# Pure_VCF.net
KiCad netlist of a schematic drawn in EAGLE
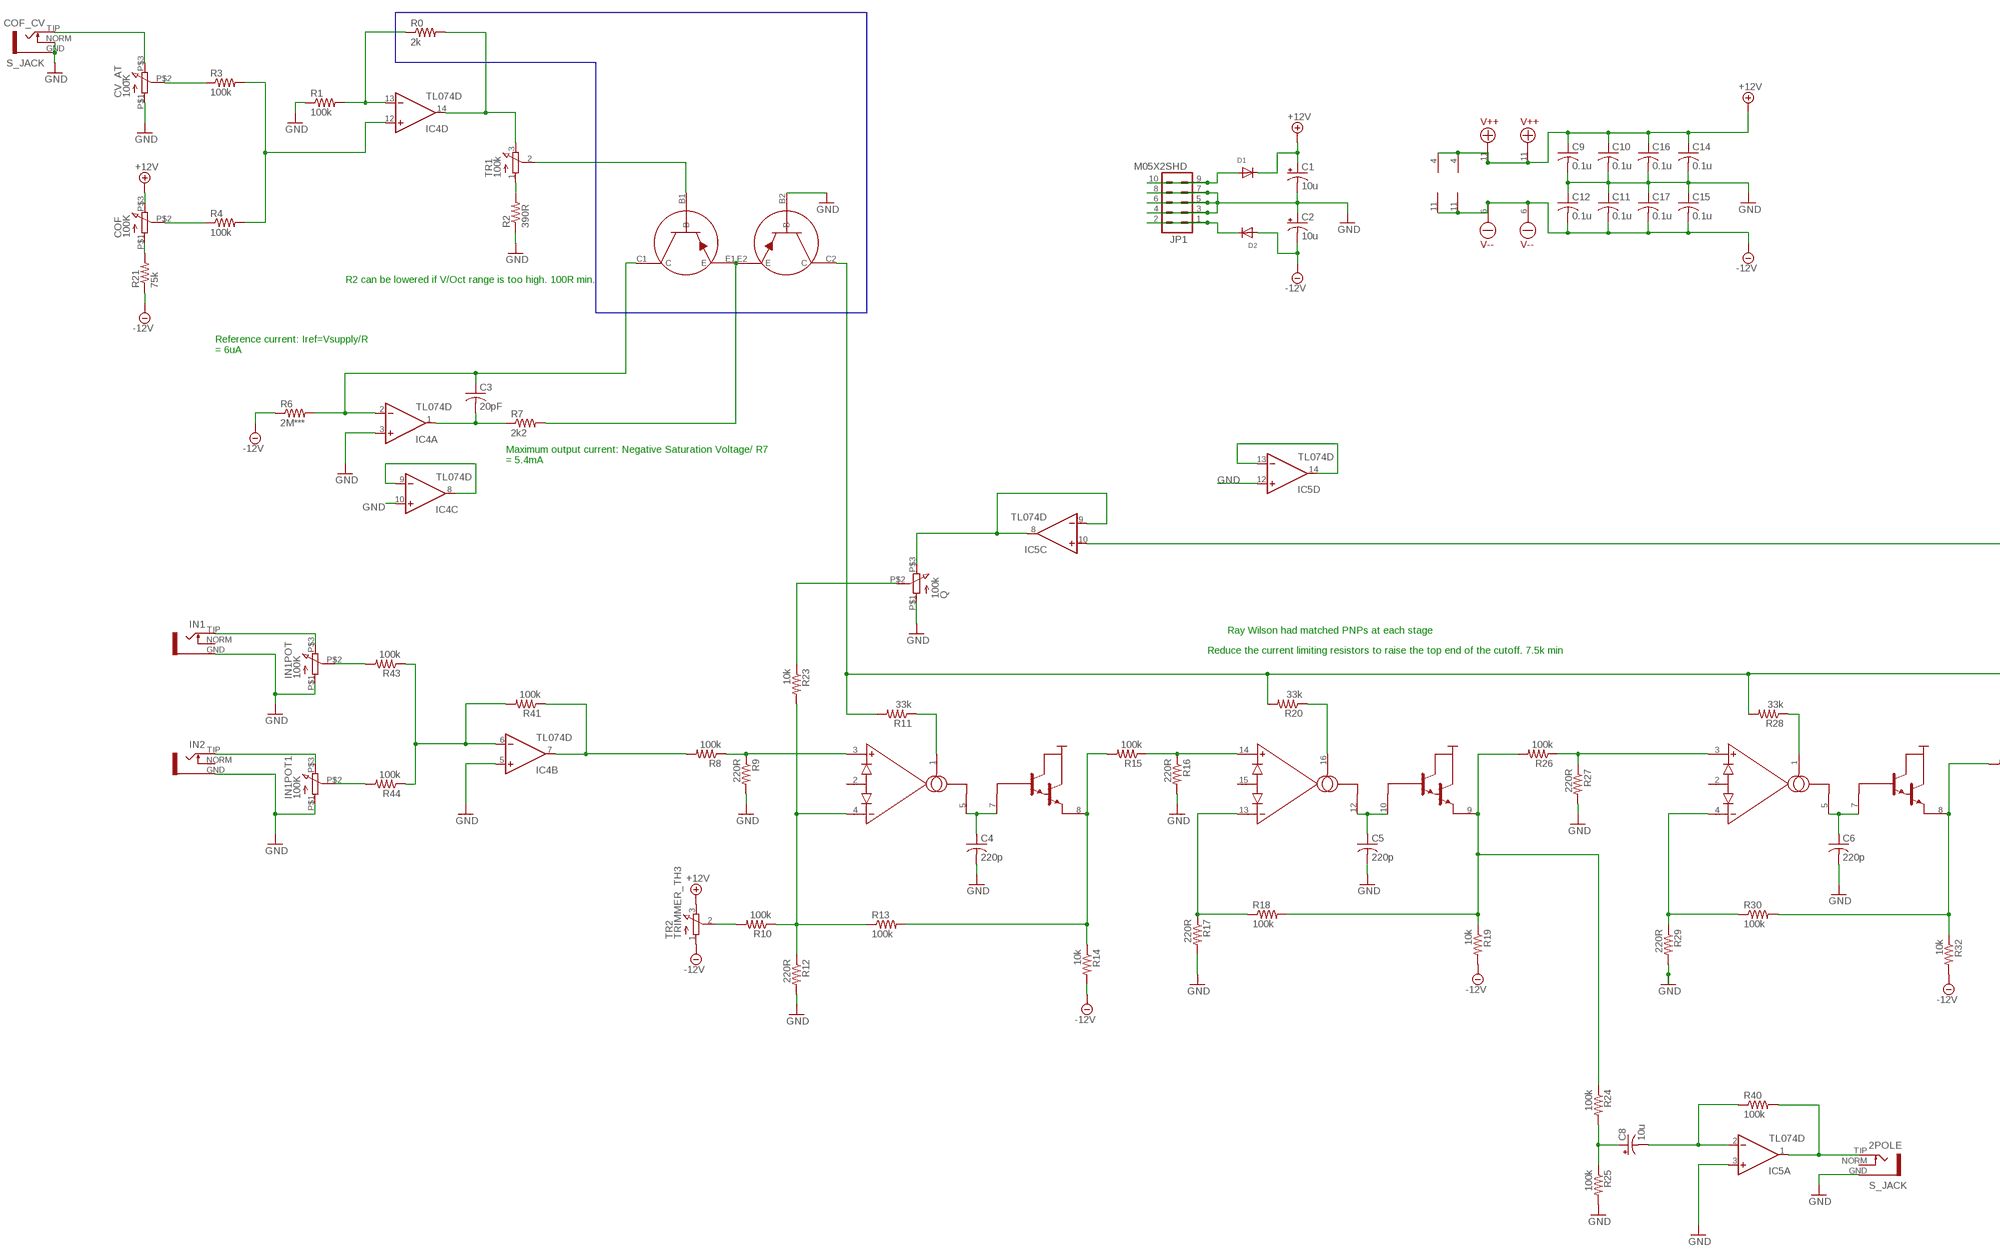
[diagram p0: schematic, sheet 1, part 1 of 2]
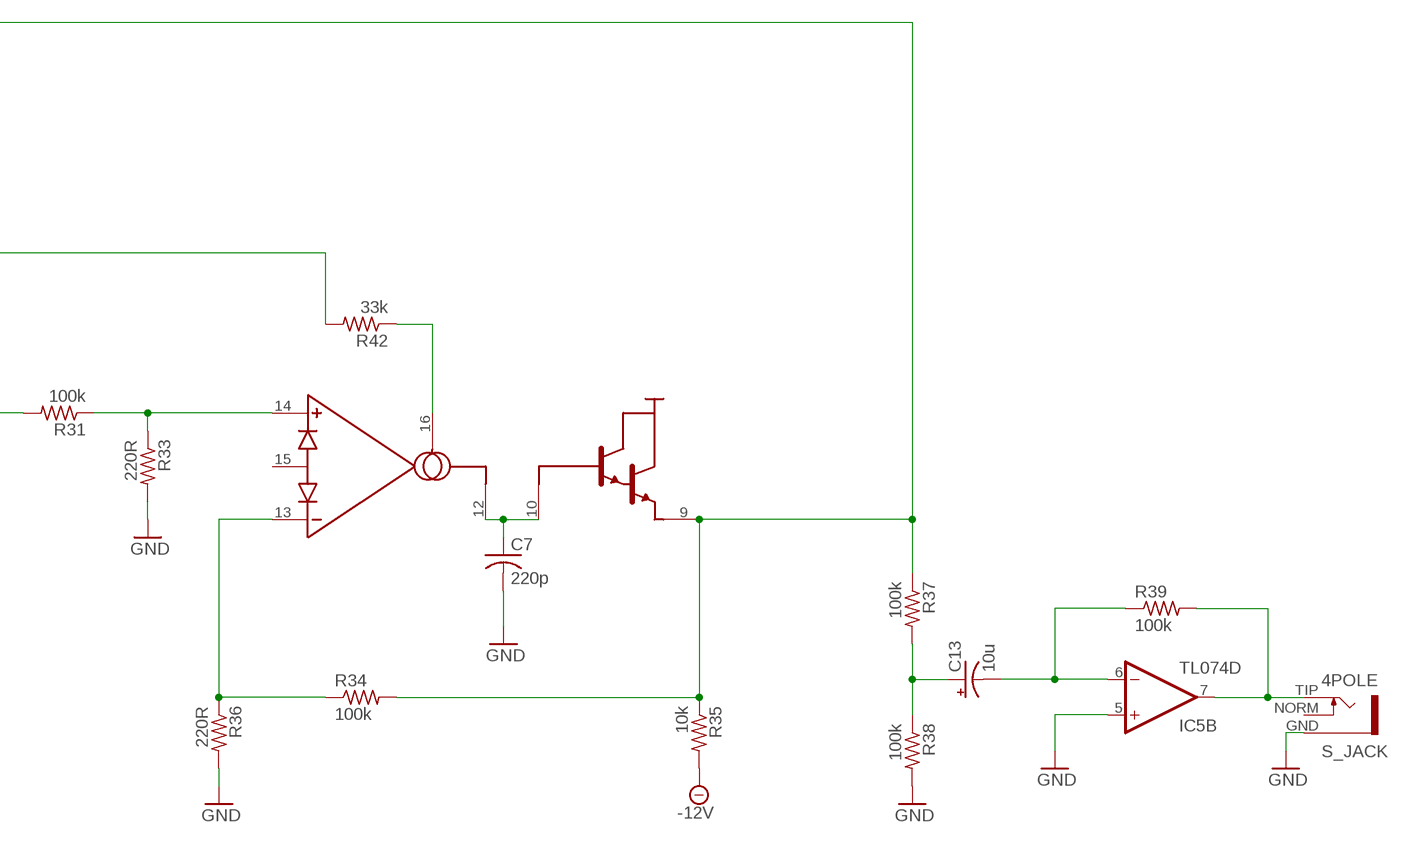
[diagram p1: schematic, sheet 1, part 2 of 2]

(export (version "E")
  (design (tool "Eeschema 10.0.6"))
  (components
    (comp (ref "2POLE")
      (value "S_JACK")
      (footprint "eagle-import:S_JACK")
      (libsource (lib "eagle-import") (part "S_JACK"))
    )
    (comp (ref "4POLE")
      (value "S_JACK")
      (footprint "eagle-import:S_JACK")
      (libsource (lib "eagle-import") (part "S_JACK"))
    )
    (comp (ref "C1")
      (value "10u")
      (footprint "eagle-import:153CLV-0505")
      (libsource (lib "eagle-import") (part "rcl_CPOL-US153CLV-0505"))
    )
    (comp (ref "C2")
      (value "10u")
      (footprint "eagle-import:153CLV-0505")
      (libsource (lib "eagle-import") (part "rcl_CPOL-US153CLV-0505"))
    )
    (comp (ref "C3")
      (value "20pF")
      (footprint "eagle-import:C0805K")
      (libsource (lib "eagle-import") (part "C-USC0805K"))
    )
    (comp (ref "C4")
      (value "220p")
      (footprint "eagle-import:C050-045X075")
      (libsource (lib "eagle-import") (part "rcl_C-US050-045X075"))
    )
    (comp (ref "C5")
      (value "220p")
      (footprint "eagle-import:C050-045X075")
      (libsource (lib "eagle-import") (part "rcl_C-US050-045X075"))
    )
    (comp (ref "C6")
      (value "220p")
      (footprint "eagle-import:C050-045X075")
      (libsource (lib "eagle-import") (part "rcl_C-US050-045X075"))
    )
    (comp (ref "C7")
      (value "220p")
      (footprint "eagle-import:C050-045X075")
      (libsource (lib "eagle-import") (part "rcl_C-US050-045X075"))
    )
    (comp (ref "C8")
      (value "10u")
      (footprint "eagle-import:153CLV-0505")
      (libsource (lib "eagle-import") (part "CPOL-US153CLV-0505"))
    )
    (comp (ref "C9")
      (value "0.1u")
      (footprint "eagle-import:C0805K")
      (libsource (lib "eagle-import") (part "rcl_C-USC0805K"))
    )
    (comp (ref "C10")
      (value "0.1u")
      (footprint "eagle-import:C0805K")
      (libsource (lib "eagle-import") (part "rcl_C-USC0805K"))
    )
    (comp (ref "C11")
      (value "0.1u")
      (footprint "eagle-import:C0805K")
      (libsource (lib "eagle-import") (part "rcl_C-USC0805K"))
    )
    (comp (ref "C12")
      (value "0.1u")
      (footprint "eagle-import:C0805K")
      (libsource (lib "eagle-import") (part "rcl_C-USC0805K"))
    )
    (comp (ref "C13")
      (value "10u")
      (footprint "eagle-import:153CLV-0505")
      (libsource (lib "eagle-import") (part "CPOL-US153CLV-0505"))
    )
    (comp (ref "C14")
      (value "0.1u")
      (footprint "eagle-import:C0805K")
      (libsource (lib "eagle-import") (part "rcl_C-USC0805K"))
    )
    (comp (ref "C15")
      (value "0.1u")
      (footprint "eagle-import:C0805K")
      (libsource (lib "eagle-import") (part "rcl_C-USC0805K"))
    )
    (comp (ref "C16")
      (value "0.1u")
      (footprint "eagle-import:C0805K")
      (libsource (lib "eagle-import") (part "rcl_C-USC0805K"))
    )
    (comp (ref "C17")
      (value "0.1u")
      (footprint "eagle-import:C0805K")
      (libsource (lib "eagle-import") (part "rcl_C-USC0805K"))
    )
    (comp (ref "COF")
      (value "100K")
      (footprint "eagle-import:POT")
      (libsource (lib "eagle-import") (part "9MMPOT"))
    )
    (comp (ref "COF_CV")
      (value "S_JACK")
      (footprint "eagle-import:S_JACK")
      (libsource (lib "eagle-import") (part "S_JACK"))
    )
    (comp (ref "CV_AT")
      (value "100K")
      (footprint "eagle-import:POT")
      (libsource (lib "eagle-import") (part "9MMPOT"))
    )
    (comp (ref "D1")
      (value "DIODESMA")
      (footprint "eagle-import:SMADIODE")
      (libsource (lib "eagle-import") (part "DIODESMA"))
    )
    (comp (ref "D2")
      (value "DIODESMA")
      (footprint "eagle-import:SMADIODE")
      (libsource (lib "eagle-import") (part "DIODESMA"))
    )
    (comp (ref "IC4")
      (value "TL074D")
      (footprint "eagle-import:SO14")
      (libsource (lib "eagle-import") (part "TL074D"))
    )
    (comp (ref "IC5")
      (value "TL074D")
      (footprint "eagle-import:SO14")
      (libsource (lib "eagle-import") (part "TL074D"))
    )
    (comp (ref "IN1")
      (value "S_JACK")
      (footprint "eagle-import:S_JACK")
      (libsource (lib "eagle-import") (part "INSTRUO_S_JACK"))
    )
    (comp (ref "IN1POT")
      (value "100K")
      (footprint "eagle-import:POT")
      (libsource (lib "eagle-import") (part "9MMPOT"))
    )
    (comp (ref "IN1POT1")
      (value "100K")
      (footprint "eagle-import:POT")
      (libsource (lib "eagle-import") (part "9MMPOT"))
    )
    (comp (ref "IN2")
      (value "S_JACK")
      (footprint "eagle-import:S_JACK")
      (libsource (lib "eagle-import") (part "INSTRUO_S_JACK"))
    )
    (comp (ref "JP1")
      (value "M05X2SHD")
      (footprint "eagle-import:2X5-SHROUDED")
      (libsource (lib "eagle-import") (part "M05X2SHD"))
    )
    (comp (ref "Q")
      (value "100k")
      (footprint "eagle-import:POT")
      (libsource (lib "eagle-import") (part "9MMPOT"))
    )
    (comp (ref "R0")
      (value "2k")
      (footprint "eagle-import:RESISTOR_TC")
      (libsource (lib "eagle-import") (part "R_TC"))
    )
    (comp (ref "R1")
      (value "100k")
      (footprint "eagle-import:R0805")
      (libsource (lib "eagle-import") (part "R-US_R0805"))
    )
    (comp (ref "R2")
      (value "390R")
      (footprint "eagle-import:R0805")
      (libsource (lib "eagle-import") (part "R-US_R0805"))
    )
    (comp (ref "R3")
      (value "100k")
      (footprint "eagle-import:R0805")
      (libsource (lib "eagle-import") (part "R-US_R0805"))
    )
    (comp (ref "R4")
      (value "100k")
      (footprint "eagle-import:R0805")
      (libsource (lib "eagle-import") (part "R-US_R0805"))
    )
    (comp (ref "R6")
      (value "2M***")
      (footprint "eagle-import:R0805")
      (libsource (lib "eagle-import") (part "R-US_R0805"))
    )
    (comp (ref "R7")
      (value "2k2")
      (footprint "eagle-import:R0805")
      (libsource (lib "eagle-import") (part "R-US_R0805"))
    )
    (comp (ref "R8")
      (value "100k")
      (footprint "eagle-import:R0805")
      (libsource (lib "eagle-import") (part "R-US_R0805"))
    )
    (comp (ref "R9")
      (value "220R")
      (footprint "eagle-import:R0805")
      (libsource (lib "eagle-import") (part "R-US_R0805"))
    )
    (comp (ref "R10")
      (value "100k")
      (footprint "eagle-import:R0805")
      (libsource (lib "eagle-import") (part "R-US_R0805"))
    )
    (comp (ref "R11")
      (value "33k")
      (footprint "eagle-import:R0805")
      (libsource (lib "eagle-import") (part "R-US_R0805"))
    )
    (comp (ref "R12")
      (value "220R")
      (footprint "eagle-import:R0805")
      (libsource (lib "eagle-import") (part "R-US_R0805"))
    )
    (comp (ref "R13")
      (value "100k")
      (footprint "eagle-import:R0805")
      (libsource (lib "eagle-import") (part "R-US_R0805"))
    )
    (comp (ref "R14")
      (value "10k")
      (footprint "eagle-import:R0805")
      (libsource (lib "eagle-import") (part "R-US_R0805"))
    )
    (comp (ref "R15")
      (value "100k")
      (footprint "eagle-import:R0805")
      (libsource (lib "eagle-import") (part "R-US_R0805"))
    )
    (comp (ref "R16")
      (value "220R")
      (footprint "eagle-import:R0805")
      (libsource (lib "eagle-import") (part "R-US_R0805"))
    )
    (comp (ref "R17")
      (value "220R")
      (footprint "eagle-import:R0805")
      (libsource (lib "eagle-import") (part "R-US_R0805"))
    )
    (comp (ref "R18")
      (value "100k")
      (footprint "eagle-import:R0805")
      (libsource (lib "eagle-import") (part "R-US_R0805"))
    )
    (comp (ref "R19")
      (value "10k")
      (footprint "eagle-import:R0805")
      (libsource (lib "eagle-import") (part "R-US_R0805"))
    )
    (comp (ref "R20")
      (value "33k")
      (footprint "eagle-import:R0805")
      (libsource (lib "eagle-import") (part "R-US_R0805"))
    )
    (comp (ref "R21")
      (value "75k")
      (footprint "eagle-import:R0805")
      (libsource (lib "eagle-import") (part "rcl_R-US_R0805"))
    )
    (comp (ref "R23")
      (value "10k")
      (footprint "eagle-import:R0805")
      (libsource (lib "eagle-import") (part "R-US_R0805"))
    )
    (comp (ref "R24")
      (value "100k")
      (footprint "eagle-import:R0805")
      (libsource (lib "eagle-import") (part "R-US_R0805"))
    )
    (comp (ref "R25")
      (value "100k")
      (footprint "eagle-import:R0805")
      (libsource (lib "eagle-import") (part "R-US_R0805"))
    )
    (comp (ref "R26")
      (value "100k")
      (footprint "eagle-import:R0805")
      (libsource (lib "eagle-import") (part "R-US_R0805"))
    )
    (comp (ref "R27")
      (value "220R")
      (footprint "eagle-import:R0805")
      (libsource (lib "eagle-import") (part "R-US_R0805"))
    )
    (comp (ref "R28")
      (value "33k")
      (footprint "eagle-import:R0805")
      (libsource (lib "eagle-import") (part "R-US_R0805"))
    )
    (comp (ref "R29")
      (value "220R")
      (footprint "eagle-import:R0805")
      (libsource (lib "eagle-import") (part "R-US_R0805"))
    )
    (comp (ref "R30")
      (value "100k")
      (footprint "eagle-import:R0805")
      (libsource (lib "eagle-import") (part "R-US_R0805"))
    )
    (comp (ref "R31")
      (value "100k")
      (footprint "eagle-import:R0805")
      (libsource (lib "eagle-import") (part "R-US_R0805"))
    )
    (comp (ref "R32")
      (value "10k")
      (footprint "eagle-import:R0805")
      (libsource (lib "eagle-import") (part "R-US_R0805"))
    )
    (comp (ref "R33")
      (value "220R")
      (footprint "eagle-import:R0805")
      (libsource (lib "eagle-import") (part "R-US_R0805"))
    )
    (comp (ref "R34")
      (value "100k")
      (footprint "eagle-import:R0805")
      (libsource (lib "eagle-import") (part "R-US_R0805"))
    )
    (comp (ref "R35")
      (value "10k")
      (footprint "eagle-import:R0805")
      (libsource (lib "eagle-import") (part "R-US_R0805"))
    )
    (comp (ref "R36")
      (value "220R")
      (footprint "eagle-import:R0805")
      (libsource (lib "eagle-import") (part "R-US_R0805"))
    )
    (comp (ref "R37")
      (value "100k")
      (footprint "eagle-import:R0805")
      (libsource (lib "eagle-import") (part "R-US_R0805"))
    )
    (comp (ref "R38")
      (value "100k")
      (footprint "eagle-import:R0805")
      (libsource (lib "eagle-import") (part "R-US_R0805"))
    )
    (comp (ref "R39")
      (value "100k")
      (footprint "eagle-import:R0805")
      (libsource (lib "eagle-import") (part "R-US_R0805"))
    )
    (comp (ref "R40")
      (value "100k")
      (footprint "eagle-import:R0805")
      (libsource (lib "eagle-import") (part "R-US_R0805"))
    )
    (comp (ref "R41")
      (value "100k")
      (footprint "eagle-import:R0805")
      (libsource (lib "eagle-import") (part "R-US_R0805"))
    )
    (comp (ref "R42")
      (value "33k")
      (footprint "eagle-import:R0805")
      (libsource (lib "eagle-import") (part "R-US_R0805"))
    )
    (comp (ref "R43")
      (value "100k")
      (footprint "eagle-import:R0805")
      (libsource (lib "eagle-import") (part "R-US_R0805"))
    )
    (comp (ref "R44")
      (value "100k")
      (footprint "eagle-import:R0805")
      (libsource (lib "eagle-import") (part "R-US_R0805"))
    )
    (comp (ref "T1")
      (value "TRANS_PAIR_PNP")
      (footprint "eagle-import:TRANS_PAIR")
      (libsource (lib "eagle-import") (part "TRANS_PAIR_PNP"))
    )
    (comp (ref "TR1")
      (value "100k")
      (footprint "eagle-import:TRIMMER_TH3")
      (libsource (lib "eagle-import") (part "TRIMMER_TH3"))
    )
    (comp (ref "TR2")
      (value "TRIMMER_TH3")
      (footprint "eagle-import:TRIMMER_TH3")
      (libsource (lib "eagle-import") (part "TRIMMER_TH3"))
    )
    (comp (ref "U$3")
      (value "LM13700")
      (footprint "eagle-import:SOIC-16_BLANK")
      (libsource (lib "eagle-import") (part "LM13700"))
    )
    (comp (ref "U$4")
      (value "LM13700")
      (footprint "eagle-import:SOIC-16_BLANK")
      (libsource (lib "eagle-import") (part "LM13700"))
    )
  )
  (nets
    (net (code "1") (name "+12V") (class "Default")
      (node (ref "C1") (pin "+") (pinfunction "+_+") (pintype "passive"))
      (node (ref "C10") (pin "1") (pinfunction "1_1") (pintype "passive"))
      (node (ref "C14") (pin "1") (pinfunction "1_1") (pintype "passive"))
      (node (ref "C16") (pin "1") (pinfunction "1_1") (pintype "passive"))
      (node (ref "C9") (pin "1") (pinfunction "1_1") (pintype "passive"))
      (node (ref "COF") (pin "P$3") (pinfunction "3_P$3") (pintype "passive"))
      (node (ref "D1") (pin "C") (pinfunction "C_C") (pintype "passive"))
      (node (ref "IC4") (pin "4") (pinfunction "V+_4") (pintype "power_in"))
      (node (ref "IC5") (pin "4") (pinfunction "V+_4") (pintype "power_in"))
      (node (ref "TR2") (pin "3") (pinfunction "3_3") (pintype "passive"))
      (node (ref "U$3") (pin "11") (pinfunction "V++_11") (pintype "bidirectional"))
      (node (ref "U$4") (pin "11") (pinfunction "V++_11") (pintype "bidirectional"))
    )
    (net (code "2") (name "-12V") (class "Default")
      (node (ref "C11") (pin "2") (pinfunction "2_2") (pintype "passive"))
      (node (ref "C12") (pin "2") (pinfunction "2_2") (pintype "passive"))
      (node (ref "C15") (pin "2") (pinfunction "2_2") (pintype "passive"))
      (node (ref "C17") (pin "2") (pinfunction "2_2") (pintype "passive"))
      (node (ref "C2") (pin "-") (pinfunction "-_-") (pintype "passive"))
      (node (ref "D2") (pin "A") (pinfunction "A_A") (pintype "passive"))
      (node (ref "IC4") (pin "11") (pinfunction "V-_11") (pintype "power_in"))
      (node (ref "IC5") (pin "11") (pinfunction "V-_11") (pintype "power_in"))
      (node (ref "R14") (pin "2") (pinfunction "2_2") (pintype "passive"))
      (node (ref "R19") (pin "2") (pinfunction "2_2") (pintype "passive"))
      (node (ref "R21") (pin "1") (pinfunction "1_1") (pintype "passive"))
      (node (ref "R32") (pin "2") (pinfunction "2_2") (pintype "passive"))
      (node (ref "R35") (pin "2") (pinfunction "2_2") (pintype "passive"))
      (node (ref "R6") (pin "1") (pinfunction "1_1") (pintype "passive"))
      (node (ref "TR2") (pin "1") (pinfunction "1_1") (pintype "passive"))
      (node (ref "U$3") (pin "6") (pinfunction "V--_6") (pintype "bidirectional"))
      (node (ref "U$4") (pin "6") (pinfunction "V--_6") (pintype "bidirectional"))
    )
    (net (code "3") (name "GND") (class "Default")
      (node (ref "2POLE") (pin "GND") (pinfunction "GND_GND") (pintype "passive"))
      (node (ref "4POLE") (pin "GND") (pinfunction "GND_GND") (pintype "passive"))
      (node (ref "C1") (pin "-") (pinfunction "-_-") (pintype "passive"))
      (node (ref "C10") (pin "2") (pinfunction "2_2") (pintype "passive"))
      (node (ref "C11") (pin "1") (pinfunction "1_1") (pintype "passive"))
      (node (ref "C12") (pin "1") (pinfunction "1_1") (pintype "passive"))
      (node (ref "C14") (pin "2") (pinfunction "2_2") (pintype "passive"))
      (node (ref "C15") (pin "1") (pinfunction "1_1") (pintype "passive"))
      (node (ref "C16") (pin "2") (pinfunction "2_2") (pintype "passive"))
      (node (ref "C17") (pin "1") (pinfunction "1_1") (pintype "passive"))
      (node (ref "C2") (pin "+") (pinfunction "+_+") (pintype "passive"))
      (node (ref "C4") (pin "2") (pinfunction "2_2") (pintype "passive"))
      (node (ref "C5") (pin "2") (pinfunction "2_2") (pintype "passive"))
      (node (ref "C6") (pin "2") (pinfunction "2_2") (pintype "passive"))
      (node (ref "C7") (pin "2") (pinfunction "2_2") (pintype "passive"))
      (node (ref "C9") (pin "2") (pinfunction "2_2") (pintype "passive"))
      (node (ref "COF_CV") (pin "GND") (pinfunction "GND_GND") (pintype "passive"))
      (node (ref "COF_CV") (pin "NORM") (pinfunction "NORM_NORM") (pintype "passive"))
      (node (ref "CV_AT") (pin "P$1") (pinfunction "1_P$1") (pintype "passive"))
      (node (ref "IC4") (pin "10") (pinfunction "+IN_10") (pintype "input"))
      (node (ref "IC4") (pin "3") (pinfunction "+IN_3") (pintype "input"))
      (node (ref "IC4") (pin "5") (pinfunction "+IN_5") (pintype "input"))
      (node (ref "IC5") (pin "12") (pinfunction "+IN_12") (pintype "input"))
      (node (ref "IC5") (pin "3") (pinfunction "+IN_3") (pintype "input"))
      (node (ref "IC5") (pin "5") (pinfunction "+IN_5") (pintype "input"))
      (node (ref "IN1") (pin "GND") (pinfunction "GND_GND") (pintype "passive"))
      (node (ref "IN1POT") (pin "P$1") (pinfunction "1_P$1") (pintype "passive"))
      (node (ref "IN1POT1") (pin "P$1") (pinfunction "1_P$1") (pintype "passive"))
      (node (ref "IN2") (pin "GND") (pinfunction "GND_GND") (pintype "passive"))
      (node (ref "JP1") (pin "3") (pinfunction "3_3") (pintype "passive"))
      (node (ref "JP1") (pin "4") (pinfunction "4_4") (pintype "passive"))
      (node (ref "JP1") (pin "5") (pinfunction "5_5") (pintype "passive"))
      (node (ref "JP1") (pin "6") (pinfunction "6_6") (pintype "passive"))
      (node (ref "JP1") (pin "7") (pinfunction "7_7") (pintype "passive"))
      (node (ref "JP1") (pin "8") (pinfunction "8_8") (pintype "passive"))
      (node (ref "Q") (pin "P$1") (pinfunction "1_P$1") (pintype "passive"))
      (node (ref "R1") (pin "1") (pinfunction "1_1") (pintype "passive"))
      (node (ref "R12") (pin "2") (pinfunction "2_2") (pintype "passive"))
      (node (ref "R16") (pin "2") (pinfunction "2_2") (pintype "passive"))
      (node (ref "R17") (pin "2") (pinfunction "2_2") (pintype "passive"))
      (node (ref "R2") (pin "1") (pinfunction "1_1") (pintype "passive"))
      (node (ref "R25") (pin "2") (pinfunction "2_2") (pintype "passive"))
      (node (ref "R27") (pin "2") (pinfunction "2_2") (pintype "passive"))
      (node (ref "R29") (pin "2") (pinfunction "2_2") (pintype "passive"))
      (node (ref "R33") (pin "2") (pinfunction "2_2") (pintype "passive"))
      (node (ref "R36") (pin "2") (pinfunction "2_2") (pintype "passive"))
      (node (ref "R38") (pin "2") (pinfunction "2_2") (pintype "passive"))
      (node (ref "R9") (pin "2") (pinfunction "2_2") (pintype "passive"))
      (node (ref "T1") (pin "B2") (pinfunction "B_B2") (pintype "bidirectional"))
    )
    (net (code "4") (name "Net-(C8-Pad+)") (class "Default")
      (node (ref "C8") (pin "+") (pinfunction "+_+") (pintype "passive"))
      (node (ref "R24") (pin "2") (pinfunction "2_2") (pintype "passive"))
      (node (ref "R25") (pin "1") (pinfunction "1_1") (pintype "passive"))
    )
    (net (code "5") (name "Net-(C13-Pad+)") (class "Default")
      (node (ref "C13") (pin "+") (pinfunction "+_+") (pintype "passive"))
      (node (ref "R37") (pin "2") (pinfunction "2_2") (pintype "passive"))
      (node (ref "R38") (pin "1") (pinfunction "1_1") (pintype "passive"))
    )
    (net (code "6") (name "Net-(COF-1)") (class "Default")
      (node (ref "COF") (pin "P$1") (pinfunction "1_P$1") (pintype "passive"))
      (node (ref "R21") (pin "2") (pinfunction "2_2") (pintype "passive"))
    )
    (net (code "7") (name "Net-(COF-2)") (class "Default")
      (node (ref "COF") (pin "P$2") (pinfunction "2_P$2") (pintype "passive"))
      (node (ref "R4") (pin "1") (pinfunction "1_1") (pintype "passive"))
    )
    (net (code "8") (name "Net-(CV_AT-2)") (class "Default")
      (node (ref "CV_AT") (pin "P$2") (pinfunction "2_P$2") (pintype "passive"))
      (node (ref "R3") (pin "1") (pinfunction "1_1") (pintype "passive"))
    )
    (net (code "9") (name "Net-(CV_AT-3)") (class "Default")
      (node (ref "COF_CV") (pin "TIP") (pinfunction "TIP_TIP") (pintype "passive"))
      (node (ref "CV_AT") (pin "P$3") (pinfunction "3_P$3") (pintype "passive"))
    )
    (net (code "10") (name "Net-(D1-PadA)") (class "Default")
      (node (ref "D1") (pin "A") (pinfunction "A_A") (pintype "passive"))
      (node (ref "JP1") (pin "10") (pinfunction "10_10") (pintype "passive"))
      (node (ref "JP1") (pin "9") (pinfunction "9_9") (pintype "passive"))
    )
    (net (code "11") (name "Net-(D2-PadC)") (class "Default")
      (node (ref "D2") (pin "C") (pinfunction "C_C") (pintype "passive"))
      (node (ref "JP1") (pin "1") (pinfunction "1_1") (pintype "passive"))
      (node (ref "JP1") (pin "2") (pinfunction "2_2") (pintype "passive"))
    )
    (net (code "12") (name "Net-(IC4A--IN)") (class "Default")
      (node (ref "C3") (pin "1") (pinfunction "1_1") (pintype "passive"))
      (node (ref "IC4") (pin "2") (pinfunction "-IN_2") (pintype "input"))
      (node (ref "R6") (pin "2") (pinfunction "2_2") (pintype "passive"))
      (node (ref "T1") (pin "C1") (pinfunction "C_C1") (pintype "bidirectional"))
    )
    (net (code "13") (name "Net-(IC4A-OUT)") (class "Default")
      (node (ref "C3") (pin "2") (pinfunction "2_2") (pintype "passive"))
      (node (ref "IC4") (pin "1") (pinfunction "OUT_1") (pintype "output"))
      (node (ref "R7") (pin "1") (pinfunction "1_1") (pintype "passive"))
    )
    (net (code "14") (name "Net-(IC4B--IN)") (class "Default")
      (node (ref "IC4") (pin "6") (pinfunction "-IN_6") (pintype "input"))
      (node (ref "R41") (pin "2") (pinfunction "2_2") (pintype "passive"))
      (node (ref "R43") (pin "1") (pinfunction "1_1") (pintype "passive"))
      (node (ref "R44") (pin "1") (pinfunction "1_1") (pintype "passive"))
    )
    (net (code "15") (name "Net-(IC4B-OUT)") (class "Default")
      (node (ref "IC4") (pin "7") (pinfunction "OUT_7") (pintype "output"))
      (node (ref "R41") (pin "1") (pinfunction "1_1") (pintype "passive"))
      (node (ref "R8") (pin "2") (pinfunction "2_2") (pintype "passive"))
    )
    (net (code "16") (name "Net-(IC4C--IN)") (class "Default")
      (node (ref "IC4") (pin "8") (pinfunction "OUT_8") (pintype "output"))
      (node (ref "IC4") (pin "9") (pinfunction "-IN_9") (pintype "input"))
    )
    (net (code "17") (name "Net-(IC4D-+IN)") (class "Default")
      (node (ref "IC4") (pin "12") (pinfunction "+IN_12") (pintype "input"))
      (node (ref "R3") (pin "2") (pinfunction "2_2") (pintype "passive"))
      (node (ref "R4") (pin "2") (pinfunction "2_2") (pintype "passive"))
    )
    (net (code "18") (name "Net-(IC4D--IN)") (class "Default")
      (node (ref "IC4") (pin "13") (pinfunction "-IN_13") (pintype "input"))
      (node (ref "R0") (pin "1") (pinfunction "1_1") (pintype "passive"))
      (node (ref "R1") (pin "2") (pinfunction "2_2") (pintype "passive"))
    )
    (net (code "19") (name "Net-(IC4D-OUT)") (class "Default")
      (node (ref "IC4") (pin "14") (pinfunction "OUT_14") (pintype "output"))
      (node (ref "R0") (pin "2") (pinfunction "2_2") (pintype "passive"))
      (node (ref "TR1") (pin "3") (pinfunction "3_3") (pintype "passive"))
    )
    (net (code "20") (name "Net-(IC5A--IN)") (class "Default")
      (node (ref "C8") (pin "-") (pinfunction "-_-") (pintype "passive"))
      (node (ref "IC5") (pin "2") (pinfunction "-IN_2") (pintype "input"))
      (node (ref "R40") (pin "1") (pinfunction "1_1") (pintype "passive"))
    )
    (net (code "21") (name "Net-(IC5A-OUT)") (class "Default")
      (node (ref "2POLE") (pin "TIP") (pinfunction "TIP_TIP") (pintype "passive"))
      (node (ref "IC5") (pin "1") (pinfunction "OUT_1") (pintype "output"))
      (node (ref "R40") (pin "2") (pinfunction "2_2") (pintype "passive"))
    )
    (net (code "22") (name "Net-(IC5B--IN)") (class "Default")
      (node (ref "C13") (pin "-") (pinfunction "-_-") (pintype "passive"))
      (node (ref "IC5") (pin "6") (pinfunction "-IN_6") (pintype "input"))
      (node (ref "R39") (pin "1") (pinfunction "1_1") (pintype "passive"))
    )
    (net (code "23") (name "Net-(IC5B-OUT)") (class "Default")
      (node (ref "4POLE") (pin "TIP") (pinfunction "TIP_TIP") (pintype "passive"))
      (node (ref "IC5") (pin "7") (pinfunction "OUT_7") (pintype "output"))
      (node (ref "R39") (pin "2") (pinfunction "2_2") (pintype "passive"))
    )
    (net (code "24") (name "Net-(IC5C-+IN)") (class "Default")
      (node (ref "IC5") (pin "10") (pinfunction "+IN_10") (pintype "input"))
      (node (ref "R34") (pin "2") (pinfunction "2_2") (pintype "passive"))
      (node (ref "R35") (pin "1") (pinfunction "1_1") (pintype "passive"))
      (node (ref "R37") (pin "1") (pinfunction "1_1") (pintype "passive"))
      (node (ref "U$4") (pin "9") (pinfunction "BUF-OUT_2_9") (pintype "bidirectional"))
    )
    (net (code "25") (name "Net-(IC5C--IN)") (class "Default")
      (node (ref "IC5") (pin "8") (pinfunction "OUT_8") (pintype "output"))
      (node (ref "IC5") (pin "9") (pinfunction "-IN_9") (pintype "input"))
      (node (ref "Q") (pin "P$3") (pinfunction "3_P$3") (pintype "passive"))
    )
    (net (code "26") (name "Net-(IC5D--IN)") (class "Default")
      (node (ref "IC5") (pin "13") (pinfunction "-IN_13") (pintype "input"))
      (node (ref "IC5") (pin "14") (pinfunction "OUT_14") (pintype "output"))
    )
    (net (code "27") (name "Net-(IN1POT-2)") (class "Default")
      (node (ref "IN1POT") (pin "P$2") (pinfunction "2_P$2") (pintype "passive"))
      (node (ref "R43") (pin "2") (pinfunction "2_2") (pintype "passive"))
    )
    (net (code "28") (name "Net-(IN1POT-3)") (class "Default")
      (node (ref "IN1") (pin "TIP") (pinfunction "TIP_TIP") (pintype "passive"))
      (node (ref "IN1POT") (pin "P$3") (pinfunction "3_P$3") (pintype "passive"))
    )
    (net (code "29") (name "Net-(IN1POT1-2)") (class "Default")
      (node (ref "IN1POT1") (pin "P$2") (pinfunction "2_P$2") (pintype "passive"))
      (node (ref "R44") (pin "2") (pinfunction "2_2") (pintype "passive"))
    )
    (net (code "30") (name "Net-(IN1POT1-3)") (class "Default")
      (node (ref "IN1POT1") (pin "P$3") (pinfunction "3_P$3") (pintype "passive"))
      (node (ref "IN2") (pin "TIP") (pinfunction "TIP_TIP") (pintype "passive"))
    )
    (net (code "31") (name "Net-(Q-2)") (class "Default")
      (node (ref "Q") (pin "P$2") (pinfunction "2_P$2") (pintype "passive"))
      (node (ref "R23") (pin "1") (pinfunction "1_1") (pintype "passive"))
    )
    (net (code "32") (name "Net-(R2-Pad2)") (class "Default")
      (node (ref "R2") (pin "2") (pinfunction "2_2") (pintype "passive"))
      (node (ref "TR1") (pin "1") (pinfunction "1_1") (pintype "passive"))
    )
    (net (code "33") (name "Net-(R10-Pad2)") (class "Default")
      (node (ref "R10") (pin "2") (pinfunction "2_2") (pintype "passive"))
      (node (ref "TR2") (pin "2") (pinfunction "2_2") (pintype "passive"))
    )
    (net (code "34") (name "Net-(T1A-B)") (class "Default")
      (node (ref "T1") (pin "B1") (pinfunction "B_B1") (pintype "bidirectional"))
      (node (ref "TR1") (pin "2") (pinfunction "2_2") (pintype "passive"))
    )
    (net (code "35") (name "Net-(T1A-E)") (class "Default")
      (node (ref "R7") (pin "2") (pinfunction "2_2") (pintype "passive"))
      (node (ref "T1") (pin "E1") (pinfunction "E_E1") (pintype "bidirectional"))
      (node (ref "T1") (pin "E2") (pinfunction "E_E2") (pintype "bidirectional"))
    )
    (net (code "36") (name "Net-(T1B-C)") (class "Default")
      (node (ref "R11") (pin "2") (pinfunction "2_2") (pintype "passive"))
      (node (ref "R20") (pin "2") (pinfunction "2_2") (pintype "passive"))
      (node (ref "R28") (pin "2") (pinfunction "2_2") (pintype "passive"))
      (node (ref "R42") (pin "2") (pinfunction "2_2") (pintype "passive"))
      (node (ref "T1") (pin "C2") (pinfunction "C_C2") (pintype "bidirectional"))
    )
    (net (code "37") (name "Net-(U$3A-BIAS-IN)") (class "Default")
      (node (ref "R11") (pin "1") (pinfunction "1_1") (pintype "passive"))
      (node (ref "U$3") (pin "1") (pinfunction "BIAS-IN_1") (pintype "bidirectional"))
    )
    (net (code "38") (name "Net-(U$3A-BUF-IN_2)") (class "Default")
      (node (ref "C4") (pin "1") (pinfunction "1_1") (pintype "passive"))
      (node (ref "U$3") (pin "5") (pinfunction "OUT_5") (pintype "bidirectional"))
      (node (ref "U$3") (pin "7") (pinfunction "BUF-IN_2_7") (pintype "bidirectional"))
    )
    (net (code "39") (name "Net-(U$3A-BUF-OUT_2)") (class "Default")
      (node (ref "R13") (pin "2") (pinfunction "2_2") (pintype "passive"))
      (node (ref "R14") (pin "1") (pinfunction "1_1") (pintype "passive"))
      (node (ref "R15") (pin "2") (pinfunction "2_2") (pintype "passive"))
      (node (ref "U$3") (pin "8") (pinfunction "BUF-OUT_2_8") (pintype "bidirectional"))
    )
    (net (code "40") (name "Net-(U$3A-IN+)") (class "Default")
      (node (ref "R8") (pin "1") (pinfunction "1_1") (pintype "passive"))
      (node (ref "R9") (pin "1") (pinfunction "1_1") (pintype "passive"))
      (node (ref "U$3") (pin "3") (pinfunction "IN+_3") (pintype "bidirectional"))
    )
    (net (code "41") (name "Net-(U$3A-IN-)") (class "Default")
      (node (ref "R10") (pin "1") (pinfunction "1_1") (pintype "passive"))
      (node (ref "R12") (pin "1") (pinfunction "1_1") (pintype "passive"))
      (node (ref "R13") (pin "1") (pinfunction "1_1") (pintype "passive"))
      (node (ref "R23") (pin "2") (pinfunction "2_2") (pintype "passive"))
      (node (ref "U$3") (pin "4") (pinfunction "IN-_4") (pintype "bidirectional"))
    )
    (net (code "42") (name "Net-(U$3B-BIAS-IN)") (class "Default")
      (node (ref "R20") (pin "1") (pinfunction "1_1") (pintype "passive"))
      (node (ref "U$3") (pin "16") (pinfunction "BIAS-IN_16") (pintype "bidirectional"))
    )
    (net (code "43") (name "Net-(U$3B-BUF-IN_2)") (class "Default")
      (node (ref "C5") (pin "1") (pinfunction "1_1") (pintype "passive"))
      (node (ref "U$3") (pin "10") (pinfunction "BUF-IN_2_10") (pintype "bidirectional"))
      (node (ref "U$3") (pin "12") (pinfunction "OUT_12") (pintype "bidirectional"))
    )
    (net (code "44") (name "Net-(U$3B-BUF-OUT_2)") (class "Default")
      (node (ref "R18") (pin "2") (pinfunction "2_2") (pintype "passive"))
      (node (ref "R19") (pin "1") (pinfunction "1_1") (pintype "passive"))
      (node (ref "R24") (pin "1") (pinfunction "1_1") (pintype "passive"))
      (node (ref "R26") (pin "2") (pinfunction "2_2") (pintype "passive"))
      (node (ref "U$3") (pin "9") (pinfunction "BUF-OUT_2_9") (pintype "bidirectional"))
    )
    (net (code "45") (name "Net-(U$3B-IN+)") (class "Default")
      (node (ref "R15") (pin "1") (pinfunction "1_1") (pintype "passive"))
      (node (ref "R16") (pin "1") (pinfunction "1_1") (pintype "passive"))
      (node (ref "U$3") (pin "14") (pinfunction "IN+_14") (pintype "bidirectional"))
    )
    (net (code "46") (name "Net-(U$3B-IN-)") (class "Default")
      (node (ref "R17") (pin "1") (pinfunction "1_1") (pintype "passive"))
      (node (ref "R18") (pin "1") (pinfunction "1_1") (pintype "passive"))
      (node (ref "U$3") (pin "13") (pinfunction "IN-_13") (pintype "bidirectional"))
    )
    (net (code "47") (name "Net-(U$4A-BIAS-IN)") (class "Default")
      (node (ref "R28") (pin "1") (pinfunction "1_1") (pintype "passive"))
      (node (ref "U$4") (pin "1") (pinfunction "BIAS-IN_1") (pintype "bidirectional"))
    )
    (net (code "48") (name "Net-(U$4A-BUF-IN_2)") (class "Default")
      (node (ref "C6") (pin "1") (pinfunction "1_1") (pintype "passive"))
      (node (ref "U$4") (pin "5") (pinfunction "OUT_5") (pintype "bidirectional"))
      (node (ref "U$4") (pin "7") (pinfunction "BUF-IN_2_7") (pintype "bidirectional"))
    )
    (net (code "49") (name "Net-(U$4A-BUF-OUT_2)") (class "Default")
      (node (ref "R30") (pin "2") (pinfunction "2_2") (pintype "passive"))
      (node (ref "R31") (pin "2") (pinfunction "2_2") (pintype "passive"))
      (node (ref "R32") (pin "1") (pinfunction "1_1") (pintype "passive"))
      (node (ref "U$4") (pin "8") (pinfunction "BUF-OUT_2_8") (pintype "bidirectional"))
    )
    (net (code "50") (name "Net-(U$4A-IN+)") (class "Default")
      (node (ref "R26") (pin "1") (pinfunction "1_1") (pintype "passive"))
      (node (ref "R27") (pin "1") (pinfunction "1_1") (pintype "passive"))
      (node (ref "U$4") (pin "3") (pinfunction "IN+_3") (pintype "bidirectional"))
    )
    (net (code "51") (name "Net-(U$4A-IN-)") (class "Default")
      (node (ref "R29") (pin "1") (pinfunction "1_1") (pintype "passive"))
      (node (ref "R30") (pin "1") (pinfunction "1_1") (pintype "passive"))
      (node (ref "U$4") (pin "4") (pinfunction "IN-_4") (pintype "bidirectional"))
    )
    (net (code "52") (name "Net-(U$4B-BIAS-IN)") (class "Default")
      (node (ref "R42") (pin "1") (pinfunction "1_1") (pintype "passive"))
      (node (ref "U$4") (pin "16") (pinfunction "BIAS-IN_16") (pintype "bidirectional"))
    )
    (net (code "53") (name "Net-(U$4B-BUF-IN_2)") (class "Default")
      (node (ref "C7") (pin "1") (pinfunction "1_1") (pintype "passive"))
      (node (ref "U$4") (pin "10") (pinfunction "BUF-IN_2_10") (pintype "bidirectional"))
      (node (ref "U$4") (pin "12") (pinfunction "OUT_12") (pintype "bidirectional"))
    )
    (net (code "54") (name "Net-(U$4B-IN+)") (class "Default")
      (node (ref "R31") (pin "1") (pinfunction "1_1") (pintype "passive"))
      (node (ref "R33") (pin "1") (pinfunction "1_1") (pintype "passive"))
      (node (ref "U$4") (pin "14") (pinfunction "IN+_14") (pintype "bidirectional"))
    )
    (net (code "55") (name "Net-(U$4B-IN-)") (class "Default")
      (node (ref "R34") (pin "1") (pinfunction "1_1") (pintype "passive"))
      (node (ref "R36") (pin "1") (pinfunction "1_1") (pintype "passive"))
      (node (ref "U$4") (pin "13") (pinfunction "IN-_13") (pintype "bidirectional"))
    )
    (net (code "56") (name "unconnected-(2POLE-PadNORM)") (class "Default")
      (node (ref "2POLE") (pin "NORM") (pinfunction "NORM_NORM") (pintype "passive"))
    )
    (net (code "57") (name "unconnected-(4POLE-PadNORM)") (class "Default")
      (node (ref "4POLE") (pin "NORM") (pinfunction "NORM_NORM") (pintype "passive"))
    )
    (net (code "58") (name "unconnected-(IN1-PadNORM)") (class "Default")
      (node (ref "IN1") (pin "NORM") (pinfunction "NORM_NORM") (pintype "passive"))
    )
    (net (code "59") (name "unconnected-(IN2-PadNORM)") (class "Default")
      (node (ref "IN2") (pin "NORM") (pinfunction "NORM_NORM") (pintype "passive"))
    )
    (net (code "60") (name "unconnected-(U$3A-D-BIAS-Pad2)") (class "Default")
      (node (ref "U$3") (pin "2") (pinfunction "D-BIAS_2") (pintype "bidirectional"))
    )
    (net (code "61") (name "unconnected-(U$3B-D-BIAS-Pad15)") (class "Default")
      (node (ref "U$3") (pin "15") (pinfunction "D-BIAS_15") (pintype "bidirectional"))
    )
    (net (code "62") (name "unconnected-(U$4A-D-BIAS-Pad2)") (class "Default")
      (node (ref "U$4") (pin "2") (pinfunction "D-BIAS_2") (pintype "bidirectional"))
    )
    (net (code "63") (name "unconnected-(U$4B-D-BIAS-Pad15)") (class "Default")
      (node (ref "U$4") (pin "15") (pinfunction "D-BIAS_15") (pintype "bidirectional"))
    )
  )
)
